# schematic.net
KiCad netlist of a schematic drawn in EAGLE
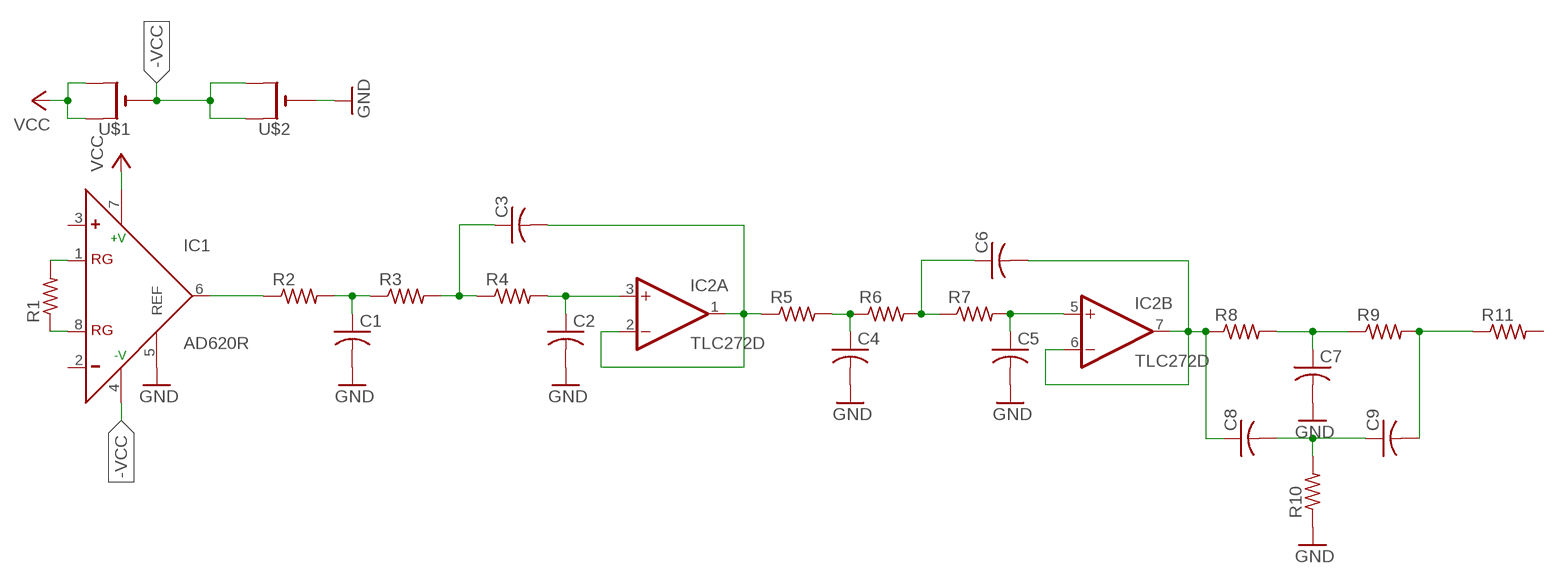
[diagram p0: schematic, sheet 1]

(export (version "E")
  (design (tool "Eeschema 10.0.6"))
  (components
    (comp (ref "C1")
      (value "C-USC0805")
      (footprint "eagle-import:C0805")
      (libsource (lib "eagle-import") (part "C-USC0805"))
    )
    (comp (ref "C2")
      (value "C-USC0805")
      (footprint "eagle-import:C0805")
      (libsource (lib "eagle-import") (part "C-USC0805"))
    )
    (comp (ref "C3")
      (value "C-USC0805")
      (footprint "eagle-import:C0805")
      (libsource (lib "eagle-import") (part "C-USC0805"))
    )
    (comp (ref "C4")
      (value "C-USC0805")
      (footprint "eagle-import:C0805")
      (libsource (lib "eagle-import") (part "C-USC0805"))
    )
    (comp (ref "C5")
      (value "C-USC0805")
      (footprint "eagle-import:C0805")
      (libsource (lib "eagle-import") (part "C-USC0805"))
    )
    (comp (ref "C6")
      (value "C-USC0805")
      (footprint "eagle-import:C0805")
      (libsource (lib "eagle-import") (part "C-USC0805"))
    )
    (comp (ref "C7")
      (value "C-USC0805")
      (footprint "eagle-import:C0805")
      (libsource (lib "eagle-import") (part "C-USC0805"))
    )
    (comp (ref "C8")
      (value "C-USC0805")
      (footprint "eagle-import:C0805")
      (libsource (lib "eagle-import") (part "C-USC0805"))
    )
    (comp (ref "C9")
      (value "C-USC0805")
      (footprint "eagle-import:C0805")
      (libsource (lib "eagle-import") (part "C-USC0805"))
    )
    (comp (ref "IC1")
      (value "AD620R")
      (footprint "eagle-import:SO8")
      (fields (field (name "MPN") "AD620AR"))
      (libsource (lib "eagle-import") (part "AD620R"))
    )
    (comp (ref "IC2")
      (value "TLC272D")
      (footprint "eagle-import:SO08")
      (libsource (lib "eagle-import") (part "TLC272D"))
    )
    (comp (ref "R1")
      (value "R-US_R0805")
      (footprint "eagle-import:R0805")
      (libsource (lib "eagle-import") (part "R-US_R0805"))
    )
    (comp (ref "R2")
      (value "R-US_R0805")
      (footprint "eagle-import:R0805")
      (libsource (lib "eagle-import") (part "R-US_R0805"))
    )
    (comp (ref "R3")
      (value "R-US_R0805")
      (footprint "eagle-import:R0805")
      (libsource (lib "eagle-import") (part "R-US_R0805"))
    )
    (comp (ref "R4")
      (value "R-US_R0805")
      (footprint "eagle-import:R0805")
      (libsource (lib "eagle-import") (part "R-US_R0805"))
    )
    (comp (ref "R5")
      (value "R-US_R0805")
      (footprint "eagle-import:R0805")
      (libsource (lib "eagle-import") (part "R-US_R0805"))
    )
    (comp (ref "R6")
      (value "R-US_R0805")
      (footprint "eagle-import:R0805")
      (libsource (lib "eagle-import") (part "R-US_R0805"))
    )
    (comp (ref "R7")
      (value "R-US_R0805")
      (footprint "eagle-import:R0805")
      (libsource (lib "eagle-import") (part "R-US_R0805"))
    )
    (comp (ref "R8")
      (value "R-US_R0805")
      (footprint "eagle-import:R0805")
      (libsource (lib "eagle-import") (part "R-US_R0805"))
    )
    (comp (ref "R9")
      (value "R-US_R0805")
      (footprint "eagle-import:R0805")
      (libsource (lib "eagle-import") (part "R-US_R0805"))
    )
    (comp (ref "R10")
      (value "R-US_R0805")
      (footprint "eagle-import:R0805")
      (libsource (lib "eagle-import") (part "R-US_R0805"))
    )
    (comp (ref "R11")
      (value "R-US_R0805")
      (footprint "eagle-import:R0805")
      (libsource (lib "eagle-import") (part "R-US_R0805"))
    )
    (comp (ref "U$1")
      (value "CR1220SMT")
      (footprint "eagle-import:CR1220-SMD")
      (libsource (lib "eagle-import") (part "CR1220SMT"))
    )
    (comp (ref "U$2")
      (value "CR1220SMT")
      (footprint "eagle-import:CR1220-SMD")
      (libsource (lib "eagle-import") (part "CR1220SMT"))
    )
  )
  (nets
    (net (code "1") (name "-VCC") (class "Default")
      (node (ref "IC1") (pin "4") (pinfunction "-V_4") (pintype "power_in"))
      (node (ref "U$1") (pin "-") (pinfunction "-_-") (pintype "passive"))
      (node (ref "U$2") (pin "+$1") (pinfunction "+_+$1") (pintype "passive"))
      (node (ref "U$2") (pin "+$2") (pinfunction "+1_+$2") (pintype "passive"))
    )
    (net (code "2") (name "GND") (class "Default")
      (node (ref "C1") (pin "2") (pinfunction "2_2") (pintype "passive"))
      (node (ref "C2") (pin "2") (pinfunction "2_2") (pintype "passive"))
      (node (ref "C4") (pin "2") (pinfunction "2_2") (pintype "passive"))
      (node (ref "C5") (pin "2") (pinfunction "2_2") (pintype "passive"))
      (node (ref "C7") (pin "2") (pinfunction "2_2") (pintype "passive"))
      (node (ref "IC1") (pin "5") (pinfunction "REF_5") (pintype "passive"))
      (node (ref "R10") (pin "1") (pinfunction "1_1") (pintype "passive"))
      (node (ref "U$2") (pin "-") (pinfunction "-_-") (pintype "passive"))
    )
    (net (code "3") (name "Net-(C1-Pad1)") (class "Default")
      (node (ref "C1") (pin "1") (pinfunction "1_1") (pintype "passive"))
      (node (ref "R2") (pin "2") (pinfunction "2_2") (pintype "passive"))
      (node (ref "R3") (pin "1") (pinfunction "1_1") (pintype "passive"))
    )
    (net (code "4") (name "Net-(C3-Pad1)") (class "Default")
      (node (ref "C3") (pin "1") (pinfunction "1_1") (pintype "passive"))
      (node (ref "R3") (pin "2") (pinfunction "2_2") (pintype "passive"))
      (node (ref "R4") (pin "1") (pinfunction "1_1") (pintype "passive"))
    )
    (net (code "5") (name "Net-(C4-Pad1)") (class "Default")
      (node (ref "C4") (pin "1") (pinfunction "1_1") (pintype "passive"))
      (node (ref "R5") (pin "2") (pinfunction "2_2") (pintype "passive"))
      (node (ref "R6") (pin "1") (pinfunction "1_1") (pintype "passive"))
    )
    (net (code "6") (name "Net-(C6-Pad1)") (class "Default")
      (node (ref "C6") (pin "1") (pinfunction "1_1") (pintype "passive"))
      (node (ref "R6") (pin "2") (pinfunction "2_2") (pintype "passive"))
      (node (ref "R7") (pin "1") (pinfunction "1_1") (pintype "passive"))
    )
    (net (code "7") (name "Net-(C7-Pad1)") (class "Default")
      (node (ref "C7") (pin "1") (pinfunction "1_1") (pintype "passive"))
      (node (ref "R8") (pin "2") (pinfunction "2_2") (pintype "passive"))
      (node (ref "R9") (pin "1") (pinfunction "1_1") (pintype "passive"))
    )
    (net (code "8") (name "Net-(C8-Pad2)") (class "Default")
      (node (ref "C8") (pin "2") (pinfunction "2_2") (pintype "passive"))
      (node (ref "C9") (pin "1") (pinfunction "1_1") (pintype "passive"))
      (node (ref "R10") (pin "2") (pinfunction "2_2") (pintype "passive"))
    )
    (net (code "9") (name "Net-(C9-Pad2)") (class "Default")
      (node (ref "C9") (pin "2") (pinfunction "2_2") (pintype "passive"))
      (node (ref "R11") (pin "1") (pinfunction "1_1") (pintype "passive"))
      (node (ref "R9") (pin "2") (pinfunction "2_2") (pintype "passive"))
    )
    (net (code "10") (name "Net-(IC1-OUT)") (class "Default")
      (node (ref "IC1") (pin "6") (pinfunction "OUT_6") (pintype "output"))
      (node (ref "R2") (pin "1") (pinfunction "1_1") (pintype "passive"))
    )
    (net (code "11") (name "Net-(IC1-RG-Pad1)") (class "Default")
      (node (ref "IC1") (pin "1") (pinfunction "RG_1") (pintype "passive"))
      (node (ref "R1") (pin "2") (pinfunction "2_2") (pintype "passive"))
    )
    (net (code "12") (name "Net-(IC1-RG-Pad8)") (class "Default")
      (node (ref "IC1") (pin "8") (pinfunction "RG_8") (pintype "passive"))
      (node (ref "R1") (pin "1") (pinfunction "1_1") (pintype "passive"))
    )
    (net (code "13") (name "Net-(IC2A-+IN)") (class "Default")
      (node (ref "C2") (pin "1") (pinfunction "1_1") (pintype "passive"))
      (node (ref "IC2") (pin "3") (pinfunction "+IN_3") (pintype "input"))
      (node (ref "R4") (pin "2") (pinfunction "2_2") (pintype "passive"))
    )
    (net (code "14") (name "Net-(IC2A--IN)") (class "Default")
      (node (ref "C3") (pin "2") (pinfunction "2_2") (pintype "passive"))
      (node (ref "IC2") (pin "1") (pinfunction "OUT_1") (pintype "output"))
      (node (ref "IC2") (pin "2") (pinfunction "-IN_2") (pintype "input"))
      (node (ref "R5") (pin "1") (pinfunction "1_1") (pintype "passive"))
    )
    (net (code "15") (name "Net-(IC2B-+IN)") (class "Default")
      (node (ref "C5") (pin "1") (pinfunction "1_1") (pintype "passive"))
      (node (ref "IC2") (pin "5") (pinfunction "+IN_5") (pintype "input"))
      (node (ref "R7") (pin "2") (pinfunction "2_2") (pintype "passive"))
    )
    (net (code "16") (name "Net-(IC2B--IN)") (class "Default")
      (node (ref "C6") (pin "2") (pinfunction "2_2") (pintype "passive"))
      (node (ref "C8") (pin "1") (pinfunction "1_1") (pintype "passive"))
      (node (ref "IC2") (pin "6") (pinfunction "-IN_6") (pintype "input"))
      (node (ref "IC2") (pin "7") (pinfunction "OUT_7") (pintype "output"))
      (node (ref "R8") (pin "1") (pinfunction "1_1") (pintype "passive"))
    )
    (net (code "17") (name "VCC") (class "Default")
      (node (ref "IC1") (pin "7") (pinfunction "+V_7") (pintype "power_in"))
      (node (ref "U$1") (pin "+$1") (pinfunction "+_+$1") (pintype "passive"))
      (node (ref "U$1") (pin "+$2") (pinfunction "+1_+$2") (pintype "passive"))
    )
    (net (code "18") (name "unconnected-(IC1-+-Pad3)") (class "Default")
      (node (ref "IC1") (pin "3") (pinfunction "+_3") (pintype "input"))
    )
    (net (code "19") (name "unconnected-(IC1---Pad2)") (class "Default")
      (node (ref "IC1") (pin "2") (pinfunction "-_2") (pintype "input"))
    )
    (net (code "20") (name "unconnected-(R11-Pad2)") (class "Default")
      (node (ref "R11") (pin "2") (pinfunction "2_2") (pintype "passive"))
    )
  )
)
